# Carloop2-v3_2.net
KiCad netlist of a schematic drawn in EAGLE
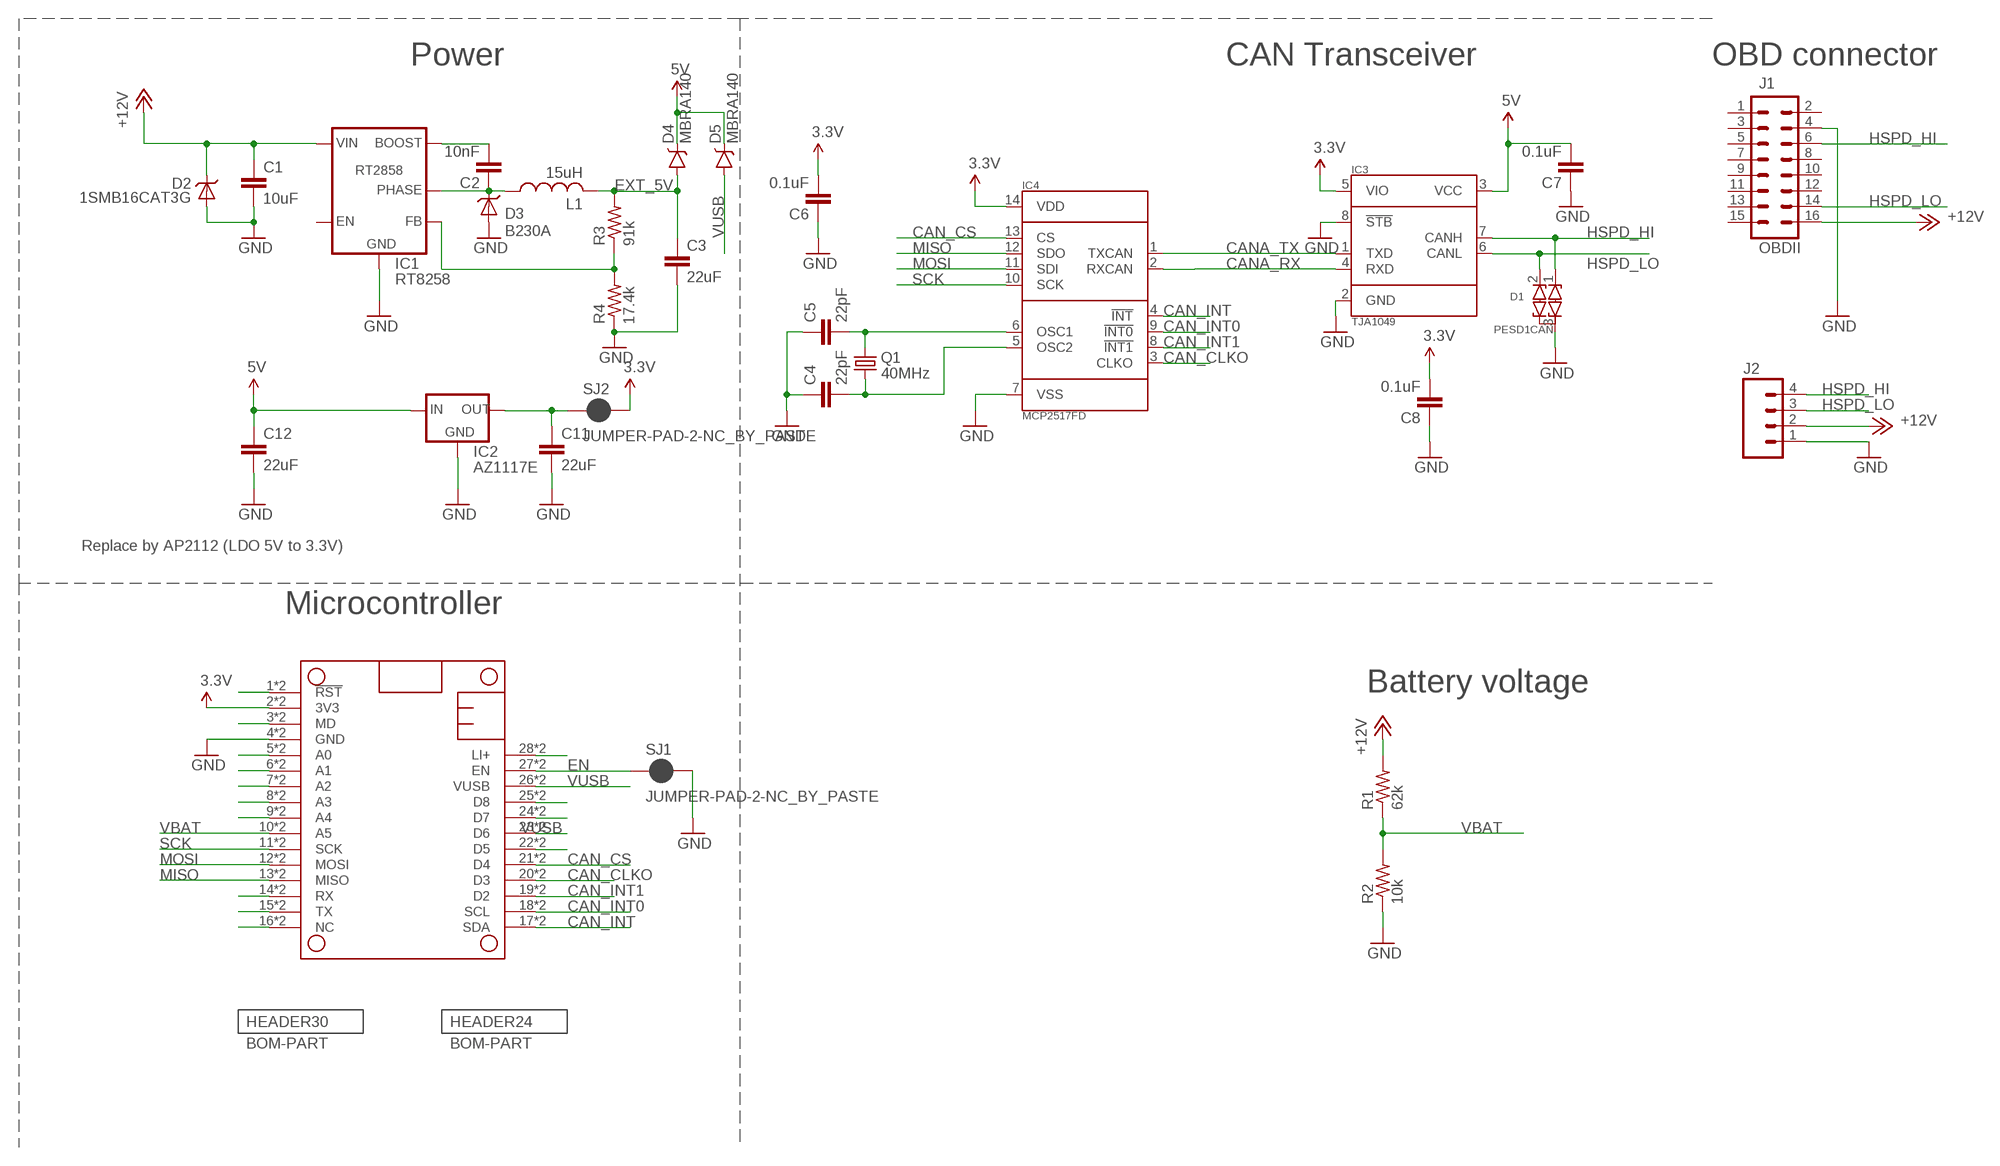
[diagram p0: schematic, sheet 1]

(export (version "E")
  (design (tool "Eeschema 10.0.6"))
  (components
    (comp (ref "C1")
      (value "10uF")
      (footprint "eagle-import:C1206")
      (fields (field (name "PARTNO") "C3216X7R1E106K160AB"))
      (libsource (lib "eagle-import") (part "C-EUC1206"))
    )
    (comp (ref "C2")
      (value "10nF")
      (footprint "eagle-import:C0603")
      (fields (field (name "PARTNO") "CGA3E2X8R1H103K080AA"))
      (libsource (lib "eagle-import") (part "C-EUC0603"))
    )
    (comp (ref "C3")
      (value "22uF")
      (footprint "eagle-import:C1206")
      (fields (field (name "PARTNO") "CL31X226KAHN3NE"))
      (libsource (lib "eagle-import") (part "C-EUC1206"))
    )
    (comp (ref "C4")
      (value "22pF")
      (footprint "eagle-import:C0603")
      (fields (field (name "PARTNO") "CC0603KRX7R9BB223"))
      (libsource (lib "eagle-import") (part "C-EUC0603"))
    )
    (comp (ref "C5")
      (value "22pF")
      (footprint "eagle-import:C0603")
      (fields (field (name "PARTNO") "CC0603KRX7R9BB223"))
      (libsource (lib "eagle-import") (part "C-EUC0603"))
    )
    (comp (ref "C6")
      (value "0.1uF")
      (footprint "eagle-import:C0603")
      (fields (field (name "PARTNO") "CC0603JRX7R7BB104"))
      (libsource (lib "eagle-import") (part "C-EUC0603"))
    )
    (comp (ref "C7")
      (value "0.1uF")
      (footprint "eagle-import:C0603")
      (fields (field (name "PARTNO") "CC0603JRX7R7BB104"))
      (libsource (lib "eagle-import") (part "C-EUC0603"))
    )
    (comp (ref "C8")
      (value "0.1uF")
      (footprint "eagle-import:C0603")
      (fields (field (name "PARTNO") "CC0603JRX7R7BB104"))
      (libsource (lib "eagle-import") (part "C-EUC0603"))
    )
    (comp (ref "C11")
      (value "22uF")
      (footprint "eagle-import:C1206")
      (fields (field (name "PARTNO") "CL31X226KAHN3NE"))
      (libsource (lib "eagle-import") (part "C-EUC1206"))
    )
    (comp (ref "C12")
      (value "22uF")
      (footprint "eagle-import:C1206")
      (fields (field (name "PARTNO") "CL31X226KAHN3NE"))
      (libsource (lib "eagle-import") (part "C-EUC1206"))
    )
    (comp (ref "D1")
      (value "PESD1CAN")
      (footprint "eagle-import:SOT23")
      (fields (field (name "PARTNO") "PESD1CAN-215"))
      (libsource (lib "eagle-import") (part "DIODE_ESD_DUAL-SOT-23"))
    )
    (comp (ref "D2")
      (value "1SMB16CAT3G")
      (footprint "eagle-import:SMB-DIODE")
      (libsource (lib "eagle-import") (part "DIODE-TVS-SMB"))
    )
    (comp (ref "D3")
      (value "B230A")
      (footprint "eagle-import:DO-214AA")
      (fields (field (name "PARTNO") "B230A-13-F"))
      (libsource (lib "eagle-import") (part "DIODE-SCHOTTKY"))
    )
    (comp (ref "D4")
      (value "MBRA140")
      (footprint "eagle-import:SMA-DIODE")
      (fields (field (name "PARTNO") "MBRA140T3G"))
      (libsource (lib "eagle-import") (part "MBRA140"))
    )
    (comp (ref "D5")
      (value "MBRA140")
      (footprint "eagle-import:SMA-DIODE")
      (fields (field (name "PARTNO") "MBRA140T3G"))
      (libsource (lib "eagle-import") (part "MBRA140"))
    )
    (comp (ref "IC1")
      (value "RT8258")
      (footprint "eagle-import:SOT-23-6")
      (fields (field (name "PARTNO") "RT8258GJ6"))
      (libsource (lib "eagle-import") (part "RT8258"))
    )
    (comp (ref "IC2")
      (value "AZ1117E")
      (footprint "eagle-import:SOT223")
      (fields (field (name "PARTNO") "AZ1117EH-3.3TRG1"))
      (libsource (lib "eagle-import") (part "AZ1117E"))
    )
    (comp (ref "IC3")
      (value "TJA1049")
      (footprint "eagle-import:SO8")
      (fields (field (name "PARTNO") "TJA1049T-118"))
      (libsource (lib "eagle-import") (part "TJA1049"))
    )
    (comp (ref "IC4")
      (value "MCP2517FD")
      (footprint "eagle-import:SOIC-14")
      (fields (field (name "PARTNO") "MCP2517FD-H/SL"))
      (libsource (lib "eagle-import") (part "MCP2517FD"))
    )
    (comp (ref "IC5")
      (value "PARTICLE_MESH_SMTDUAL")
      (footprint "eagle-import:FEATHERWING_SMT2")
      (libsource (lib "eagle-import") (part "PARTICLE_MESH_SMTDUAL"))
    )
    (comp (ref "J1")
      (value "OBDII")
      (footprint "eagle-import:OBDII-COMTECH")
      (fields (field (name "PARTNO") "OBD-II"))
      (libsource (lib "eagle-import") (part "M08X2-OBDII-COMTECH"))
    )
    (comp (ref "J2")
      (value "M04SCREW")
      (footprint "eagle-import:SCREWTERMINAL-3.5MM-4")
      (fields (field (name "PARTNO") "OSTTE040104"))
      (libsource (lib "eagle-import") (part "M04SCREW"))
    )
    (comp (ref "L1")
      (value "15uH")
      (footprint "eagle-import:NR8040")
      (fields (field (name "PARTNO") "NR8040T150M"))
      (libsource (lib "eagle-import") (part "L-US"))
    )
    (comp (ref "Q1")
      (value "40MHz")
      (footprint "eagle-import:CRYSTAL-SMD-5X3")
      (fields (field (name "PARTNO") "ECS-400-12-30B-AGM-TR"))
      (libsource (lib "eagle-import") (part "CRYSTAL5X3"))
    )
    (comp (ref "R1")
      (value "62k")
      (footprint "eagle-import:R0603")
      (fields (field (name "PARTNO") "ERA-3AEB623V"))
      (libsource (lib "eagle-import") (part "R-US_R0603"))
    )
    (comp (ref "R2")
      (value "10k")
      (footprint "eagle-import:R0603")
      (fields (field (name "PARTNO") "ERA-3AED103V"))
      (libsource (lib "eagle-import") (part "R-US_R0603"))
    )
    (comp (ref "R3")
      (value "91k")
      (footprint "eagle-import:R0603")
      (fields (field (name "PARTNO") "ERA-3ARB913V"))
      (libsource (lib "eagle-import") (part "R-US_R0603"))
    )
    (comp (ref "R4")
      (value "17.4k")
      (footprint "eagle-import:R0603")
      (fields (field (name "PARTNO") "ERJ-3EKF1742V"))
      (libsource (lib "eagle-import") (part "R-US_R0603"))
    )
    (comp (ref "SJ1")
      (value "JUMPER-PAD-2-NC_BY_PASTE")
      (footprint "eagle-import:PAD-JUMPER-2-NC_BY_PASTE_YES_SILK")
      (libsource (lib "eagle-import") (part "JUMPER-PAD-2-NC_BY_PASTE"))
    )
    (comp (ref "SJ2")
      (value "JUMPER-PAD-2-NC_BY_PASTE")
      (footprint "eagle-import:PAD-JUMPER-2-NC_BY_PASTE_YES_SILK")
      (libsource (lib "eagle-import") (part "JUMPER-PAD-2-NC_BY_PASTE"))
    )
  )
  (nets
    (net (code "1") (name "+12V") (class "Default")
      (node (ref "C1") (pin "1") (pinfunction "1_1") (pintype "passive"))
      (node (ref "D2") (pin "C") (pinfunction "C_C") (pintype "passive"))
      (node (ref "IC1") (pin "5") (pinfunction "VIN_5") (pintype "input"))
      (node (ref "J1") (pin "16") (pinfunction "16_16") (pintype "passive"))
      (node (ref "J2") (pin "2") (pinfunction "2_2") (pintype "passive"))
      (node (ref "R1") (pin "2") (pinfunction "2_2") (pintype "passive"))
    )
    (net (code "2") (name "/CANA_RX") (class "Default")
      (node (ref "IC3") (pin "4") (pinfunction "RXD_4") (pintype "bidirectional"))
      (node (ref "IC4") (pin "2") (pinfunction "RXCAN_2") (pintype "bidirectional"))
    )
    (net (code "3") (name "/CANA_TX") (class "Default")
      (node (ref "IC3") (pin "1") (pinfunction "TXD_1") (pintype "bidirectional"))
      (node (ref "IC4") (pin "1") (pinfunction "TXCAN_1") (pintype "bidirectional"))
    )
    (net (code "4") (name "/CAN_CLKO") (class "Default")
      (node (ref "IC4") (pin "3") (pinfunction "CLKO_3") (pintype "bidirectional"))
      (node (ref "IC5") (pin "20") (pinfunction "D3_20") (pintype "bidirectional"))
      (node (ref "IC5") (pin "20'") (pinfunction "D3_20'") (pintype "bidirectional"))
    )
    (net (code "5") (name "/CAN_CS") (class "Default")
      (node (ref "IC4") (pin "13") (pinfunction "CS_13") (pintype "bidirectional"))
      (node (ref "IC5") (pin "21") (pinfunction "D4_21") (pintype "bidirectional"))
      (node (ref "IC5") (pin "21'") (pinfunction "D4_21'") (pintype "bidirectional"))
    )
    (net (code "6") (name "/CAN_INT") (class "Default")
      (node (ref "IC4") (pin "4") (pinfunction "~{INT}_4") (pintype "bidirectional"))
      (node (ref "IC5") (pin "17") (pinfunction "SDA_17") (pintype "bidirectional"))
      (node (ref "IC5") (pin "17'") (pinfunction "SDA_17'") (pintype "bidirectional"))
    )
    (net (code "7") (name "/CAN_INT0") (class "Default")
      (node (ref "IC4") (pin "9") (pinfunction "~{INT0}_9") (pintype "bidirectional"))
      (node (ref "IC5") (pin "18") (pinfunction "SCL_18") (pintype "bidirectional"))
      (node (ref "IC5") (pin "18'") (pinfunction "SCL_18'") (pintype "bidirectional"))
    )
    (net (code "8") (name "/CAN_INT1") (class "Default")
      (node (ref "IC4") (pin "8") (pinfunction "~{INT1}_8") (pintype "bidirectional"))
      (node (ref "IC5") (pin "19") (pinfunction "D2_19") (pintype "bidirectional"))
      (node (ref "IC5") (pin "19'") (pinfunction "D2_19'") (pintype "bidirectional"))
    )
    (net (code "9") (name "/EN") (class "Default")
      (node (ref "IC5") (pin "27") (pinfunction "EN_27") (pintype "passive"))
      (node (ref "IC5") (pin "27'") (pinfunction "EN_27'") (pintype "passive"))
      (node (ref "SJ1") (pin "1") (pinfunction "1_1") (pintype "passive"))
    )
    (net (code "10") (name "/EXT_5V") (class "Default")
      (node (ref "C3") (pin "1") (pinfunction "1_1") (pintype "passive"))
      (node (ref "D4") (pin "A") (pinfunction "A_A") (pintype "passive"))
      (node (ref "L1") (pin "P$2") (pinfunction "2_P$2") (pintype "passive"))
      (node (ref "R3") (pin "2") (pinfunction "2_2") (pintype "passive"))
    )
    (net (code "11") (name "/HSPD_HI") (class "Default")
      (node (ref "D1") (pin "1") (pinfunction "C1_1") (pintype "power_in"))
      (node (ref "IC3") (pin "7") (pinfunction "CANH_7") (pintype "bidirectional"))
      (node (ref "J1") (pin "6") (pinfunction "6_6") (pintype "passive"))
      (node (ref "J2") (pin "4") (pinfunction "4_4") (pintype "passive"))
    )
    (net (code "12") (name "/HSPD_LO") (class "Default")
      (node (ref "D1") (pin "2") (pinfunction "C2_2") (pintype "power_in"))
      (node (ref "IC3") (pin "6") (pinfunction "CANL_6") (pintype "bidirectional"))
      (node (ref "J1") (pin "14") (pinfunction "14_14") (pintype "passive"))
      (node (ref "J2") (pin "3") (pinfunction "3_3") (pintype "passive"))
    )
    (net (code "13") (name "/MISO") (class "Default")
      (node (ref "IC4") (pin "12") (pinfunction "SDO_12") (pintype "bidirectional"))
      (node (ref "IC5") (pin "13") (pinfunction "MISO_13") (pintype "bidirectional"))
      (node (ref "IC5") (pin "13'") (pinfunction "MISO_13'") (pintype "bidirectional"))
    )
    (net (code "14") (name "/MOSI") (class "Default")
      (node (ref "IC4") (pin "11") (pinfunction "SDI_11") (pintype "bidirectional"))
      (node (ref "IC5") (pin "12") (pinfunction "MOSI_12") (pintype "bidirectional"))
      (node (ref "IC5") (pin "12'") (pinfunction "MOSI_12'") (pintype "bidirectional"))
    )
    (net (code "15") (name "/SCK") (class "Default")
      (node (ref "IC4") (pin "10") (pinfunction "SCK_10") (pintype "bidirectional"))
      (node (ref "IC5") (pin "11") (pinfunction "SCK_11") (pintype "bidirectional"))
      (node (ref "IC5") (pin "11'") (pinfunction "SCK_11'") (pintype "bidirectional"))
    )
    (net (code "16") (name "/VBAT") (class "Default")
      (node (ref "IC5") (pin "10") (pinfunction "A5_10") (pintype "bidirectional"))
      (node (ref "IC5") (pin "10'") (pinfunction "A5_10'") (pintype "bidirectional"))
      (node (ref "R1") (pin "1") (pinfunction "1_1") (pintype "passive"))
      (node (ref "R2") (pin "2") (pinfunction "2_2") (pintype "passive"))
    )
    (net (code "17") (name "/VUSB") (class "Default")
      (node (ref "D5") (pin "A") (pinfunction "A_A") (pintype "passive"))
      (node (ref "IC5") (pin "26") (pinfunction "VUSB_26") (pintype "power_in"))
      (node (ref "IC5") (pin "26'") (pinfunction "VUSB_26'") (pintype "power_in"))
    )
    (net (code "18") (name "3.3V") (class "Default")
      (node (ref "C6") (pin "2") (pinfunction "2_2") (pintype "passive"))
      (node (ref "C8") (pin "2") (pinfunction "2_2") (pintype "passive"))
      (node (ref "IC3") (pin "5") (pinfunction "VIO_5") (pintype "bidirectional"))
      (node (ref "IC4") (pin "14") (pinfunction "VDD_14") (pintype "bidirectional"))
      (node (ref "IC5") (pin "2") (pinfunction "3V3_2") (pintype "power_in"))
      (node (ref "IC5") (pin "2'") (pinfunction "3V3_2'") (pintype "power_in"))
      (node (ref "SJ2") (pin "2") (pinfunction "2_2") (pintype "passive"))
    )
    (net (code "19") (name "5V") (class "Default")
      (node (ref "C12") (pin "1") (pinfunction "1_1") (pintype "passive"))
      (node (ref "C7") (pin "2") (pinfunction "2_2") (pintype "passive"))
      (node (ref "D4") (pin "C") (pinfunction "C_C") (pintype "passive"))
      (node (ref "D5") (pin "C") (pinfunction "C_C") (pintype "passive"))
      (node (ref "IC2") (pin "3") (pinfunction "IN_3") (pintype "input"))
      (node (ref "IC3") (pin "3") (pinfunction "VCC_3") (pintype "bidirectional"))
    )
    (net (code "20") (name "GND") (class "Default")
      (node (ref "C1") (pin "2") (pinfunction "2_2") (pintype "passive"))
      (node (ref "C11") (pin "2") (pinfunction "2_2") (pintype "passive"))
      (node (ref "C12") (pin "2") (pinfunction "2_2") (pintype "passive"))
      (node (ref "C3") (pin "2") (pinfunction "2_2") (pintype "passive"))
      (node (ref "C4") (pin "1") (pinfunction "1_1") (pintype "passive"))
      (node (ref "C5") (pin "1") (pinfunction "1_1") (pintype "passive"))
      (node (ref "C6") (pin "1") (pinfunction "1_1") (pintype "passive"))
      (node (ref "C7") (pin "1") (pinfunction "1_1") (pintype "passive"))
      (node (ref "C8") (pin "1") (pinfunction "1_1") (pintype "passive"))
      (node (ref "D1") (pin "3") (pinfunction "COM_3") (pintype "power_in"))
      (node (ref "D2") (pin "A") (pinfunction "A_A") (pintype "passive"))
      (node (ref "D3") (pin "+") (pinfunction "A_+") (pintype "passive"))
      (node (ref "IC1") (pin "2") (pinfunction "GND_2") (pintype "input"))
      (node (ref "IC2") (pin "1") (pinfunction "GND_1") (pintype "input"))
      (node (ref "IC2") (pin "4") (pinfunction "GND_4") (pintype "input"))
      (node (ref "IC3") (pin "2") (pinfunction "GND_2") (pintype "bidirectional"))
      (node (ref "IC3") (pin "8") (pinfunction "~{STB}_8") (pintype "bidirectional"))
      (node (ref "IC4") (pin "7") (pinfunction "VSS_7") (pintype "bidirectional"))
      (node (ref "IC5") (pin "4") (pinfunction "GND_4") (pintype "power_in"))
      (node (ref "IC5") (pin "4'") (pinfunction "GND_4'") (pintype "power_in"))
      (node (ref "J1") (pin "4") (pinfunction "4_4") (pintype "passive"))
      (node (ref "J2") (pin "1") (pinfunction "1_1") (pintype "passive"))
      (node (ref "R2") (pin "1") (pinfunction "1_1") (pintype "passive"))
      (node (ref "R4") (pin "1") (pinfunction "1_1") (pintype "passive"))
      (node (ref "SJ1") (pin "2") (pinfunction "2_2") (pintype "passive"))
    )
    (net (code "21") (name "Net-(D3-C)") (class "Default")
      (node (ref "C2") (pin "1") (pinfunction "1_1") (pintype "passive"))
      (node (ref "D3") (pin "-") (pinfunction "C_-") (pintype "passive"))
      (node (ref "IC1") (pin "6") (pinfunction "PHASE_6") (pintype "passive"))
      (node (ref "L1") (pin "P$1") (pinfunction "1_P$1") (pintype "passive"))
    )
    (net (code "22") (name "Net-(IC1-BOOST)") (class "Default")
      (node (ref "C2") (pin "2") (pinfunction "2_2") (pintype "passive"))
      (node (ref "IC1") (pin "1") (pinfunction "BOOST_1") (pintype "passive"))
    )
    (net (code "23") (name "Net-(IC1-FB)") (class "Default")
      (node (ref "IC1") (pin "3") (pinfunction "FB_3") (pintype "passive"))
      (node (ref "R3") (pin "1") (pinfunction "1_1") (pintype "passive"))
      (node (ref "R4") (pin "2") (pinfunction "2_2") (pintype "passive"))
    )
    (net (code "24") (name "Net-(IC2-OUT)") (class "Default")
      (node (ref "C11") (pin "1") (pinfunction "1_1") (pintype "passive"))
      (node (ref "IC2") (pin "2") (pinfunction "OUT_2") (pintype "passive"))
      (node (ref "SJ2") (pin "1") (pinfunction "1_1") (pintype "passive"))
    )
    (net (code "25") (name "Net-(IC4-OSC1)") (class "Default")
      (node (ref "C5") (pin "2") (pinfunction "2_2") (pintype "passive"))
      (node (ref "IC4") (pin "6") (pinfunction "OSC1_6") (pintype "bidirectional"))
      (node (ref "Q1") (pin "3") (pinfunction "2_3") (pintype "passive"))
    )
    (net (code "26") (name "Net-(IC4-OSC2)") (class "Default")
      (node (ref "C4") (pin "2") (pinfunction "2_2") (pintype "passive"))
      (node (ref "IC4") (pin "5") (pinfunction "OSC2_5") (pintype "bidirectional"))
      (node (ref "Q1") (pin "1") (pinfunction "1_1") (pintype "passive"))
    )
    (net (code "27") (name "Net-(IC5-A0-Pad5')") (class "Default")
      (node (ref "IC5") (pin "5") (pinfunction "A0_5") (pintype "bidirectional"))
      (node (ref "IC5") (pin "5'") (pinfunction "A0_5'") (pintype "bidirectional"))
    )
    (net (code "28") (name "Net-(IC5-A1-Pad6')") (class "Default")
      (node (ref "IC5") (pin "6") (pinfunction "A1_6") (pintype "bidirectional"))
      (node (ref "IC5") (pin "6'") (pinfunction "A1_6'") (pintype "bidirectional"))
    )
    (net (code "29") (name "Net-(IC5-A2-Pad7')") (class "Default")
      (node (ref "IC5") (pin "7") (pinfunction "A2_7") (pintype "bidirectional"))
      (node (ref "IC5") (pin "7'") (pinfunction "A2_7'") (pintype "bidirectional"))
    )
    (net (code "30") (name "Net-(IC5-A3-Pad8')") (class "Default")
      (node (ref "IC5") (pin "8") (pinfunction "A3_8") (pintype "bidirectional"))
      (node (ref "IC5") (pin "8'") (pinfunction "A3_8'") (pintype "bidirectional"))
    )
    (net (code "31") (name "Net-(IC5-A4-Pad9')") (class "Default")
      (node (ref "IC5") (pin "9") (pinfunction "A4_9") (pintype "bidirectional"))
      (node (ref "IC5") (pin "9'") (pinfunction "A4_9'") (pintype "bidirectional"))
    )
    (net (code "32") (name "Net-(IC5-D5-Pad22')") (class "Default")
      (node (ref "IC5") (pin "22") (pinfunction "D5_22") (pintype "bidirectional"))
      (node (ref "IC5") (pin "22'") (pinfunction "D5_22'") (pintype "bidirectional"))
    )
    (net (code "33") (name "Net-(IC5-D6-Pad23')") (class "Default")
      (node (ref "IC5") (pin "23") (pinfunction "D6_23") (pintype "bidirectional"))
      (node (ref "IC5") (pin "23'") (pinfunction "D6_23'") (pintype "bidirectional"))
    )
    (net (code "34") (name "Net-(IC5-D7-Pad24')") (class "Default")
      (node (ref "IC5") (pin "24") (pinfunction "D7_24") (pintype "bidirectional"))
      (node (ref "IC5") (pin "24'") (pinfunction "D7_24'") (pintype "bidirectional"))
    )
    (net (code "35") (name "Net-(IC5-D8-Pad25')") (class "Default")
      (node (ref "IC5") (pin "25") (pinfunction "D8_25") (pintype "bidirectional"))
      (node (ref "IC5") (pin "25'") (pinfunction "D8_25'") (pintype "bidirectional"))
    )
    (net (code "36") (name "Net-(IC5-LI+-Pad28')") (class "Default")
      (node (ref "IC5") (pin "28") (pinfunction "LI+_28") (pintype "power_in"))
      (node (ref "IC5") (pin "28'") (pinfunction "LI+_28'") (pintype "power_in"))
    )
    (net (code "37") (name "Net-(IC5-MD-Pad3')") (class "Default")
      (node (ref "IC5") (pin "3") (pinfunction "MD_3") (pintype "bidirectional"))
      (node (ref "IC5") (pin "3'") (pinfunction "MD_3'") (pintype "bidirectional"))
    )
    (net (code "38") (name "Net-(IC5-NC-Pad16')") (class "Default")
      (node (ref "IC5") (pin "16") (pinfunction "NC_16") (pintype "passive"))
      (node (ref "IC5") (pin "16'") (pinfunction "NC_16'") (pintype "passive"))
    )
    (net (code "39") (name "Net-(IC5-RX-Pad14')") (class "Default")
      (node (ref "IC5") (pin "14") (pinfunction "RX_14") (pintype "bidirectional"))
      (node (ref "IC5") (pin "14'") (pinfunction "RX_14'") (pintype "bidirectional"))
    )
    (net (code "40") (name "Net-(IC5-TX-Pad15')") (class "Default")
      (node (ref "IC5") (pin "15") (pinfunction "TX_15") (pintype "bidirectional"))
      (node (ref "IC5") (pin "15'") (pinfunction "TX_15'") (pintype "bidirectional"))
    )
    (net (code "41") (name "Net-(IC5-~{RST}-Pad1')") (class "Default")
      (node (ref "IC5") (pin "1") (pinfunction "~{RST}_1") (pintype "input"))
      (node (ref "IC5") (pin "1'") (pinfunction "~{RST}_1'") (pintype "input"))
    )
    (net (code "42") (name "unconnected-(IC1-EN-Pad4)") (class "Default")
      (node (ref "IC1") (pin "4") (pinfunction "EN_4") (pintype "input"))
    )
    (net (code "43") (name "unconnected-(J1-Pad1)") (class "Default")
      (node (ref "J1") (pin "1") (pinfunction "1_1") (pintype "passive"))
    )
    (net (code "44") (name "unconnected-(J1-Pad2)") (class "Default")
      (node (ref "J1") (pin "2") (pinfunction "2_2") (pintype "passive"))
    )
    (net (code "45") (name "unconnected-(J1-Pad3)") (class "Default")
      (node (ref "J1") (pin "3") (pinfunction "3_3") (pintype "passive"))
    )
    (net (code "46") (name "unconnected-(J1-Pad5)") (class "Default")
      (node (ref "J1") (pin "5") (pinfunction "5_5") (pintype "passive"))
    )
    (net (code "47") (name "unconnected-(J1-Pad7)") (class "Default")
      (node (ref "J1") (pin "7") (pinfunction "7_7") (pintype "passive"))
    )
    (net (code "48") (name "unconnected-(J1-Pad8)") (class "Default")
      (node (ref "J1") (pin "8") (pinfunction "8_8") (pintype "passive"))
    )
    (net (code "49") (name "unconnected-(J1-Pad9)") (class "Default")
      (node (ref "J1") (pin "9") (pinfunction "9_9") (pintype "passive"))
    )
    (net (code "50") (name "unconnected-(J1-Pad10)") (class "Default")
      (node (ref "J1") (pin "10") (pinfunction "10_10") (pintype "passive"))
    )
    (net (code "51") (name "unconnected-(J1-Pad11)") (class "Default")
      (node (ref "J1") (pin "11") (pinfunction "11_11") (pintype "passive"))
    )
    (net (code "52") (name "unconnected-(J1-Pad12)") (class "Default")
      (node (ref "J1") (pin "12") (pinfunction "12_12") (pintype "passive"))
    )
    (net (code "53") (name "unconnected-(J1-Pad13)") (class "Default")
      (node (ref "J1") (pin "13") (pinfunction "13_13") (pintype "passive"))
    )
    (net (code "54") (name "unconnected-(J1-Pad15)") (class "Default")
      (node (ref "J1") (pin "15") (pinfunction "15_15") (pintype "passive"))
    )
  )
)
